# SwitchDecoder.net
KiCad netlist of a schematic drawn in Altium Designer
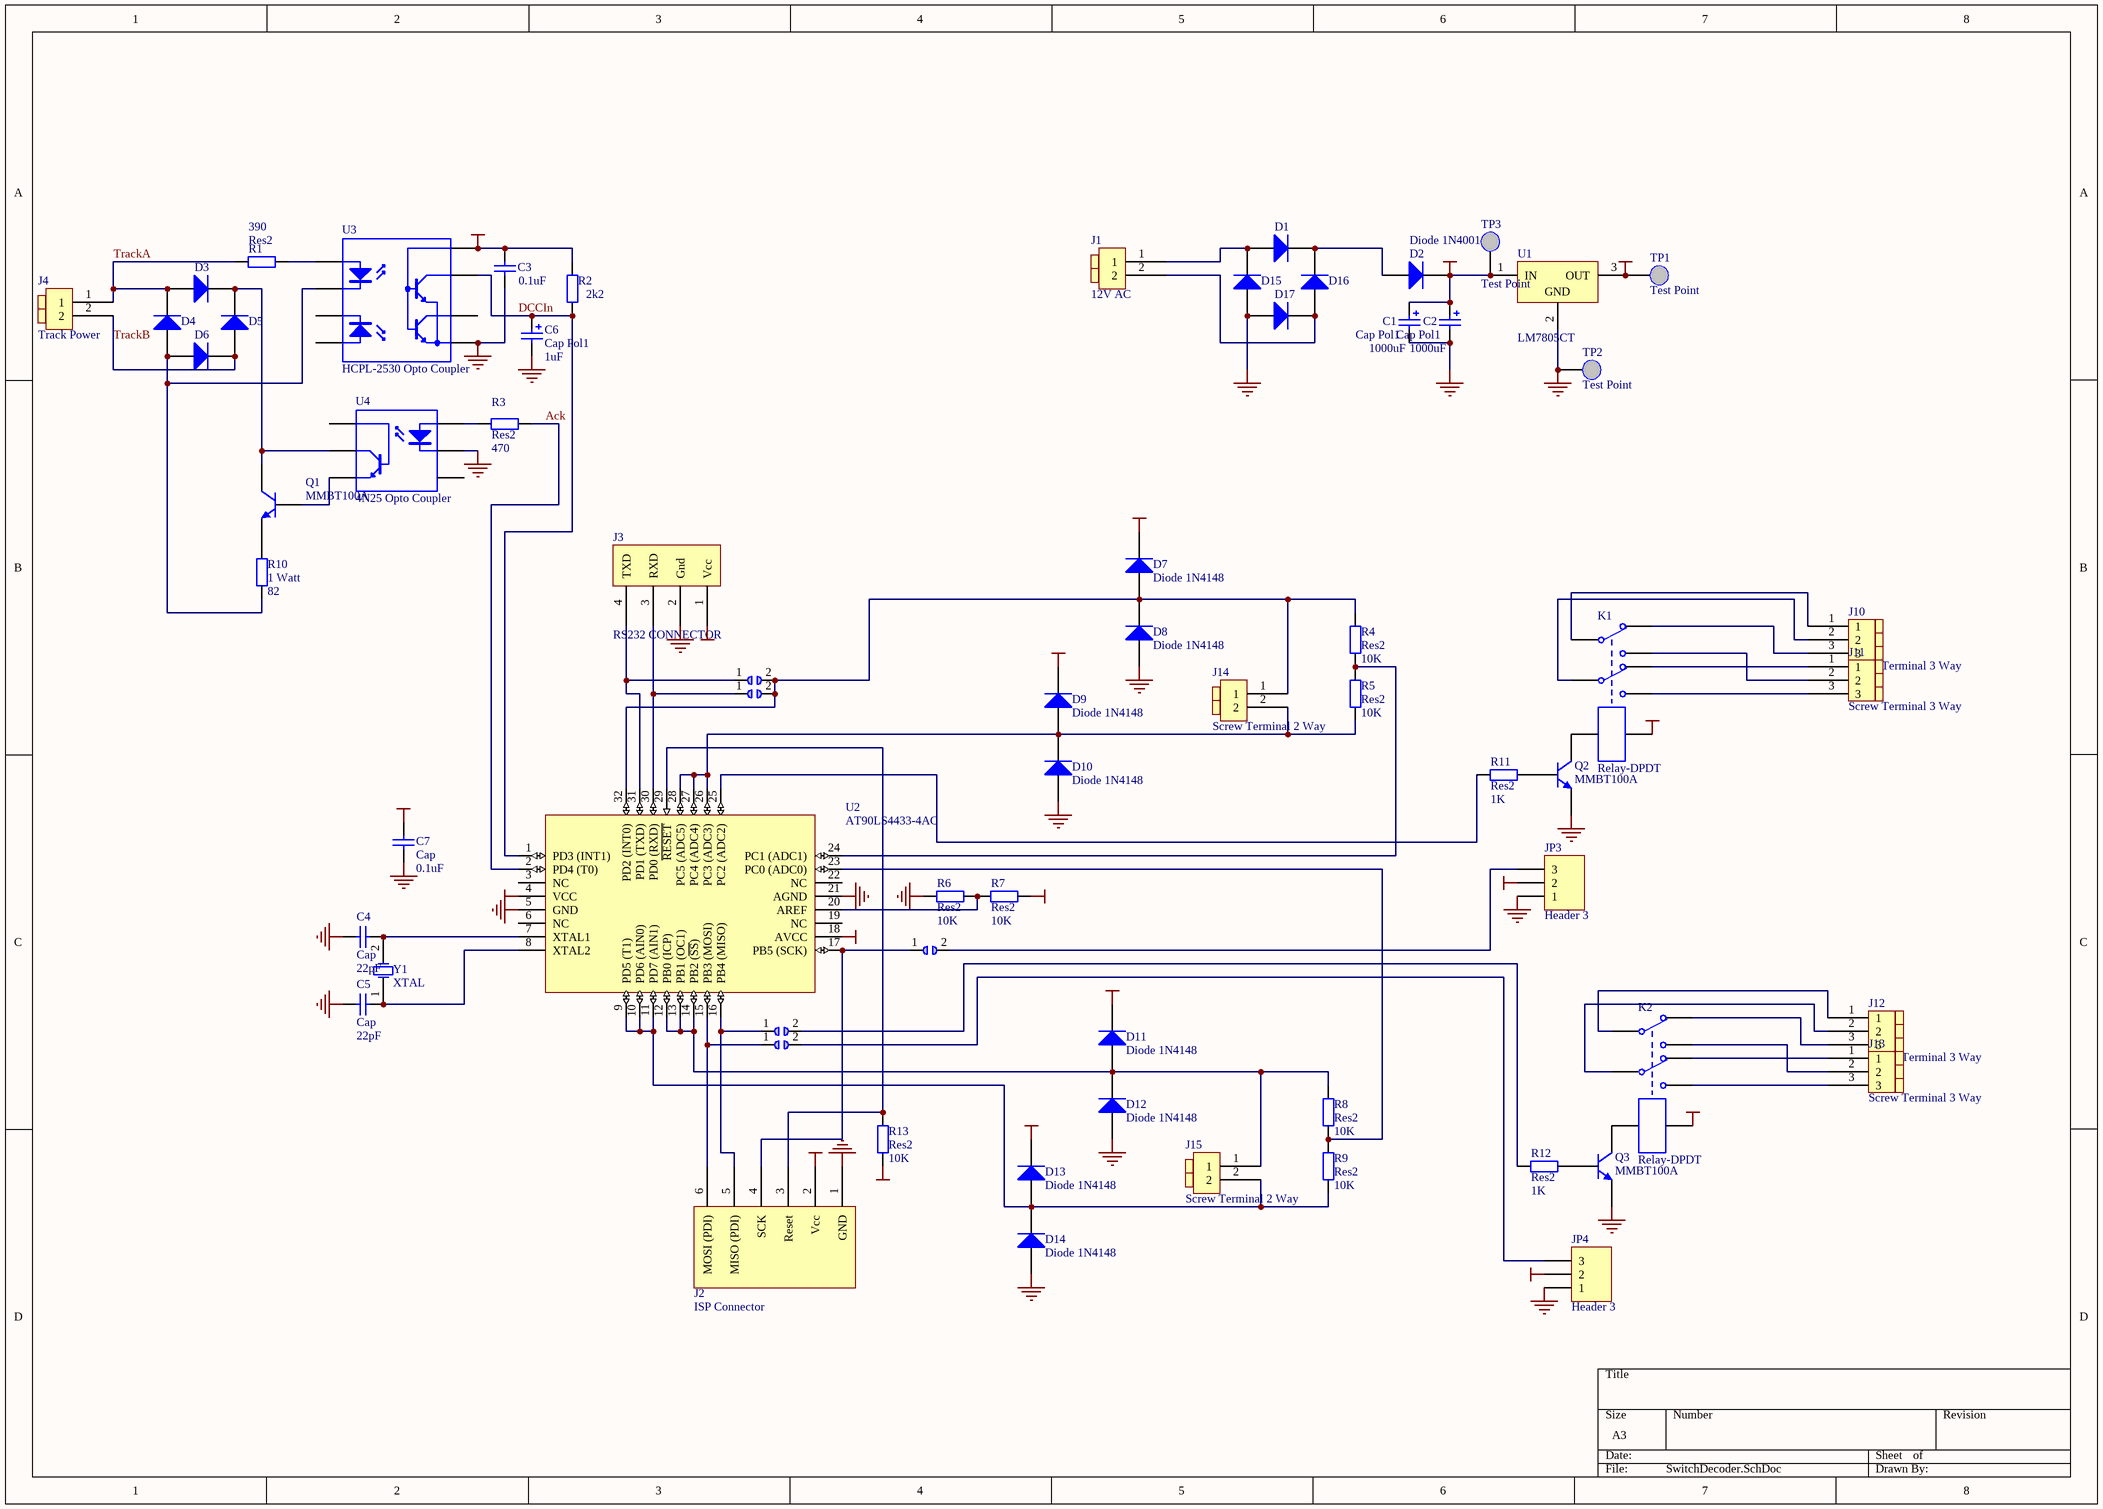
[diagram p0: SwitchDecoder.SchDoc]

(export (version "E")
  (design (tool "Eeschema 10.0.6"))
  (components
    (comp (ref "C1")
      (value "Cap Pol1")
      (footprint "CAPPR5-10X10.5")
      (description "Polarized Capacitor (Radial)")
      (fields (field (name "ALTIUM_VALUE") "1000uF") (field (name "PUBLISHER") "Altium Limited"))
      (libsource (lib "Miscellaneous Devices") (part "Cap Pol1"))
    )
    (comp (ref "C2")
      (value "Cap Pol1")
      (footprint "CAPPR5-10X10.5")
      (description "Polarized Capacitor (Radial)")
      (fields (field (name "ALTIUM_VALUE") "1000uF") (field (name "PUBLISHER") "Altium Limited"))
      (libsource (lib "Miscellaneous Devices") (part "Cap Pol1"))
    )
    (comp (ref "C3")
      (value "0.1uF")
      (footprint "CC2012-0805")
      (description "Capacitor")
      (fields (field (name "Comment") "Cap") (field (name "PUBLISHER") "Altium Limited"))
      (libsource (lib "Miscellaneous Devices") (part "Cap"))
    )
    (comp (ref "C4")
      (value "Cap")
      (footprint "CC2012-0805")
      (description "Capacitor")
      (fields (field (name "ALTIUM_VALUE") "22pF") (field (name "PUBLISHER") "Altium Limited"))
      (libsource (lib "Miscellaneous Devices") (part "Cap"))
    )
    (comp (ref "C5")
      (value "Cap")
      (footprint "CC2012-0805")
      (description "Capacitor")
      (fields (field (name "ALTIUM_VALUE") "22pF") (field (name "PUBLISHER") "Altium Limited"))
      (libsource (lib "Miscellaneous Devices") (part "Cap"))
    )
    (comp (ref "C6")
      (value "Cap Pol1")
      (footprint "CC3216-1206")
      (description "Polarized Capacitor (Radial)")
      (fields (field (name "ALTIUM_VALUE") "1uF") (field (name "PUBLISHER") "Altium Limited"))
      (libsource (lib "Miscellaneous Devices") (part "Cap Pol1"))
    )
    (comp (ref "C7")
      (value "Cap")
      (footprint "CC2012-0805")
      (description "Capacitor")
      (fields (field (name "ALTIUM_VALUE") "0.1uF") (field (name "PUBLISHER") "Altium Limited"))
      (libsource (lib "Miscellaneous Devices") (part "Cap"))
    )
    (comp (ref "D1")
      (value "Diode 1N4004")
      (footprint "DIO10.46-5.3x2.8")
      (description "1 Amp General Purpose Rectifier")
      (fields (field (name "PUBLISHER") "Altium Limited"))
      (libsource (lib "Miscellaneous Devices") (part "Diode 1N4004"))
    )
    (comp (ref "D2")
      (value "Diode 1N4001")
      (footprint "DIO10.46-5.3x2.8")
      (description "1 Amp General Purpose Rectifier")
      (fields (field (name "PUBLISHER") "Altium Limited"))
      (libsource (lib "Miscellaneous Devices") (part "Diode 1N4001"))
    )
    (comp (ref "D3")
      (value "Diode 1N4148")
      (footprint "DIO7.1-3.9x1.9")
      (description "High Conductance Fast Diode")
      (fields (field (name "PUBLISHER") "Altium Limited"))
      (libsource (lib "Miscellaneous Devices") (part "Diode 1N4148"))
    )
    (comp (ref "D4")
      (value "Diode 1N4148")
      (footprint "DIO7.1-3.9x1.9")
      (description "High Conductance Fast Diode")
      (fields (field (name "PUBLISHER") "Altium Limited"))
      (libsource (lib "Miscellaneous Devices") (part "Diode 1N4148"))
    )
    (comp (ref "D5")
      (value "Diode 1N4148")
      (footprint "DIO7.1-3.9x1.9")
      (description "High Conductance Fast Diode")
      (fields (field (name "PUBLISHER") "Altium Limited"))
      (libsource (lib "Miscellaneous Devices") (part "Diode 1N4148"))
    )
    (comp (ref "D6")
      (value "Diode 1N4148")
      (footprint "DIO7.1-3.9x1.9")
      (description "High Conductance Fast Diode")
      (fields (field (name "PUBLISHER") "Altium Limited"))
      (libsource (lib "Miscellaneous Devices") (part "Diode 1N4148"))
    )
    (comp (ref "D7")
      (value "Diode 1N4148")
      (footprint "DIO7.1-3.9x1.9")
      (description "High Conductance Fast Diode")
      (fields (field (name "PUBLISHER") "Altium Limited"))
      (libsource (lib "Miscellaneous Devices") (part "Diode 1N4148"))
    )
    (comp (ref "D8")
      (value "Diode 1N4148")
      (footprint "DIO7.1-3.9x1.9")
      (description "High Conductance Fast Diode")
      (fields (field (name "PUBLISHER") "Altium Limited"))
      (libsource (lib "Miscellaneous Devices") (part "Diode 1N4148"))
    )
    (comp (ref "D9")
      (value "Diode 1N4148")
      (footprint "DIO7.1-3.9x1.9")
      (description "High Conductance Fast Diode")
      (fields (field (name "PUBLISHER") "Altium Limited"))
      (libsource (lib "Miscellaneous Devices") (part "Diode 1N4148"))
    )
    (comp (ref "D10")
      (value "Diode 1N4148")
      (footprint "DIO7.1-3.9x1.9")
      (description "High Conductance Fast Diode")
      (fields (field (name "PUBLISHER") "Altium Limited"))
      (libsource (lib "Miscellaneous Devices") (part "Diode 1N4148"))
    )
    (comp (ref "D11")
      (value "Diode 1N4148")
      (footprint "DIO7.1-3.9x1.9")
      (description "High Conductance Fast Diode")
      (fields (field (name "PUBLISHER") "Altium Limited"))
      (libsource (lib "Miscellaneous Devices") (part "Diode 1N4148"))
    )
    (comp (ref "D12")
      (value "Diode 1N4148")
      (footprint "DIO7.1-3.9x1.9")
      (description "High Conductance Fast Diode")
      (fields (field (name "PUBLISHER") "Altium Limited"))
      (libsource (lib "Miscellaneous Devices") (part "Diode 1N4148"))
    )
    (comp (ref "D13")
      (value "Diode 1N4148")
      (footprint "DIO7.1-3.9x1.9")
      (description "High Conductance Fast Diode")
      (fields (field (name "PUBLISHER") "Altium Limited"))
      (libsource (lib "Miscellaneous Devices") (part "Diode 1N4148"))
    )
    (comp (ref "D14")
      (value "Diode 1N4148")
      (footprint "DIO7.1-3.9x1.9")
      (description "High Conductance Fast Diode")
      (fields (field (name "PUBLISHER") "Altium Limited"))
      (libsource (lib "Miscellaneous Devices") (part "Diode 1N4148"))
    )
    (comp (ref "D15")
      (value "Diode 1N4004")
      (footprint "DIO10.46-5.3x2.8")
      (description "1 Amp General Purpose Rectifier")
      (fields (field (name "PUBLISHER") "Altium Limited"))
      (libsource (lib "Miscellaneous Devices") (part "Diode 1N4004"))
    )
    (comp (ref "D16")
      (value "Diode 1N4004")
      (footprint "DIO10.46-5.3x2.8")
      (description "1 Amp General Purpose Rectifier")
      (fields (field (name "PUBLISHER") "Altium Limited"))
      (libsource (lib "Miscellaneous Devices") (part "Diode 1N4004"))
    )
    (comp (ref "D17")
      (value "Diode 1N4004")
      (footprint "DIO10.46-5.3x2.8")
      (description "1 Amp General Purpose Rectifier")
      (fields (field (name "PUBLISHER") "Altium Limited"))
      (libsource (lib "Miscellaneous Devices") (part "Diode 1N4004"))
    )
    (comp (ref "J1")
      (value "12V AC")
      (footprint "Screw Terminal 2 way 0.2")
      (libsource (lib "Custom") (part "Screw Terminal 2 Way"))
    )
    (comp (ref "J2")
      (value "ISP Connector")
      (footprint "0.1 SIP 6 PIN")
      (libsource (lib "Custom") (part "ISP Connector"))
    )
    (comp (ref "J3")
      (value "RS232 CONNECTOR")
      (footprint "0.1 SIP 4 PIN")
      (libsource (lib "Custom") (part "RS232 CONNECTOR"))
    )
    (comp (ref "J4")
      (value "Track Power")
      (footprint "Screw Terminal 2 way 0.2")
      (libsource (lib "Custom") (part "Screw Terminal 2 Way"))
    )
    (comp (ref "J5") (value "Jumper") (footprint "Jumper") (libsource (lib "Custom") (part "Jumper")))
    (comp (ref "J6") (value "Jumper") (footprint "Jumper") (libsource (lib "Custom") (part "Jumper")))
    (comp (ref "J7") (value "Jumper") (footprint "Jumper") (libsource (lib "Custom") (part "Jumper")))
    (comp (ref "J8") (value "Jumper") (footprint "Jumper") (libsource (lib "Custom") (part "Jumper")))
    (comp (ref "J9") (value "Jumper") (footprint "Jumper") (libsource (lib "Custom") (part "Jumper")))
    (comp (ref "J10")
      (value "Screw Terminal 3 Way")
      (footprint "Screw Terminal 3 way 0.2")
      (libsource (lib "Custom") (part "Screw Terminal 3 Way"))
    )
    (comp (ref "J11")
      (value "Screw Terminal 3 Way")
      (footprint "Screw Terminal 3 way 0.2")
      (libsource (lib "Custom") (part "Screw Terminal 3 Way"))
    )
    (comp (ref "J12")
      (value "Screw Terminal 3 Way")
      (footprint "Screw Terminal 3 way 0.2")
      (libsource (lib "Custom") (part "Screw Terminal 3 Way"))
    )
    (comp (ref "J13")
      (value "Screw Terminal 3 Way")
      (footprint "Screw Terminal 3 way 0.2")
      (libsource (lib "Custom") (part "Screw Terminal 3 Way"))
    )
    (comp (ref "J14")
      (value "Screw Terminal 2 Way")
      (footprint "Screw Terminal 2 way 0.2")
      (libsource (lib "Custom") (part "Screw Terminal 2 Way"))
    )
    (comp (ref "J15")
      (value "Screw Terminal 2 Way")
      (footprint "Screw Terminal 2 way 0.2")
      (libsource (lib "Custom") (part "Screw Terminal 2 Way"))
    )
    (comp (ref "JP3")
      (value "Header 3")
      (footprint "HDR1X3")
      (description "Header, 3-Pin")
      (fields (field (name "PUBLISHER") "Altium Limited"))
      (libsource (lib "Miscellaneous Connectors") (part "Header 3"))
    )
    (comp (ref "JP4")
      (value "Header 3")
      (footprint "HDR1X3")
      (description "Header, 3-Pin")
      (fields (field (name "PUBLISHER") "Altium Limited"))
      (libsource (lib "Miscellaneous Connectors") (part "Header 3"))
    )
    (comp (ref "K1")
      (value "Relay-DPDT")
      (footprint "RelayDPDT")
      (description "Dual-Pole Dual-Throw Relay")
      (fields (field (name "PUBLISHER") "Altium Limited"))
      (libsource (lib "Miscellaneous Devices") (part "Relay-DPDT"))
    )
    (comp (ref "K2")
      (value "Relay-DPDT")
      (footprint "RelayDPDT")
      (description "Dual-Pole Dual-Throw Relay")
      (fields (field (name "PUBLISHER") "Altium Limited"))
      (libsource (lib "Miscellaneous Devices") (part "Relay-DPDT"))
    )
    (comp (ref "Q1")
      (value "MMBT100A")
      (footprint "SO-G3")
      (description "General Purpose Amplifier NPN Silicon")
      (fields (field (name "PUBLISHER") "Altium Limited"))
      (libsource (lib "Custom") (part "MMBT100A"))
    )
    (comp (ref "Q2")
      (value "MMBT100A")
      (footprint "SO-G3")
      (description "General Purpose Amplifier NPN Silicon")
      (fields (field (name "PUBLISHER") "Altium Limited"))
      (libsource (lib "Custom") (part "MMBT100A"))
    )
    (comp (ref "Q3")
      (value "MMBT100A")
      (footprint "SO-G3")
      (description "General Purpose Amplifier NPN Silicon")
      (fields (field (name "PUBLISHER") "Altium Limited"))
      (libsource (lib "Custom") (part "MMBT100A"))
    )
    (comp (ref "R1")
      (value "Res2")
      (footprint "CR2012-0805")
      (description "Resistor")
      (fields (field (name "ALTIUM_VALUE") "390") (field (name "PUBLISHER") "Altium Limited"))
      (libsource (lib "") (part "Res2_3"))
    )
    (comp (ref "R2")
      (value "2k2")
      (footprint "CR2012-0805")
      (description "Resistor")
      (fields (field (name "Comment") "Res2") (field (name "PUBLISHER") "Altium Limited"))
      (libsource (lib "Miscellaneous Devices") (part "Res2"))
    )
    (comp (ref "R3")
      (value "Res2")
      (footprint "CR2012-0805")
      (description "Resistor")
      (fields (field (name "ALTIUM_VALUE") "470") (field (name "PUBLISHER") "Altium Limited"))
      (libsource (lib "") (part "Res2_1"))
    )
    (comp (ref "R4")
      (value "Res2")
      (footprint "CR2012-0805")
      (description "Resistor")
      (fields (field (name "ALTIUM_VALUE") "10K") (field (name "PUBLISHER") "Altium Limited"))
      (libsource (lib "Miscellaneous Devices") (part "Res2"))
    )
    (comp (ref "R5")
      (value "Res2")
      (footprint "CR2012-0805")
      (description "Resistor")
      (fields (field (name "ALTIUM_VALUE") "10K") (field (name "PUBLISHER") "Altium Limited"))
      (libsource (lib "Miscellaneous Devices") (part "Res2"))
    )
    (comp (ref "R6")
      (value "Res2")
      (footprint "CR2012-0805")
      (description "Resistor")
      (fields (field (name "ALTIUM_VALUE") "10K") (field (name "PUBLISHER") "Altium Limited"))
      (libsource (lib "") (part "Res2_1"))
    )
    (comp (ref "R7")
      (value "Res2")
      (footprint "CR2012-0805")
      (description "Resistor")
      (fields (field (name "ALTIUM_VALUE") "10K") (field (name "PUBLISHER") "Altium Limited"))
      (libsource (lib "") (part "Res2_1"))
    )
    (comp (ref "R8")
      (value "Res2")
      (footprint "CR2012-0805")
      (description "Resistor")
      (fields (field (name "ALTIUM_VALUE") "10K") (field (name "PUBLISHER") "Altium Limited"))
      (libsource (lib "Miscellaneous Devices") (part "Res2"))
    )
    (comp (ref "R9")
      (value "Res2")
      (footprint "CR2012-0805")
      (description "Resistor")
      (fields (field (name "ALTIUM_VALUE") "10K") (field (name "PUBLISHER") "Altium Limited"))
      (libsource (lib "Miscellaneous Devices") (part "Res2"))
    )
    (comp (ref "R10")
      (value "1 Watt")
      (footprint "AXIAL-0.6")
      (description "Resistor")
      (fields (field (name "ALTIUM_VALUE") "82") (field (name "PUBLISHER") "Altium Limited"))
      (libsource (lib "") (part "Res2_2"))
    )
    (comp (ref "R11")
      (value "Res2")
      (footprint "CR2012-0805")
      (description "Resistor")
      (fields (field (name "ALTIUM_VALUE") "1K") (field (name "PUBLISHER") "Altium Limited"))
      (libsource (lib "") (part "Res2_1"))
    )
    (comp (ref "R12")
      (value "Res2")
      (footprint "CR2012-0805")
      (description "Resistor")
      (fields (field (name "ALTIUM_VALUE") "1K") (field (name "PUBLISHER") "Altium Limited"))
      (libsource (lib "") (part "Res2_1"))
    )
    (comp (ref "R13")
      (value "Res2")
      (footprint "CR2012-0805")
      (description "Resistor")
      (fields (field (name "ALTIUM_VALUE") "10K") (field (name "PUBLISHER") "Altium Limited"))
      (libsource (lib "Miscellaneous Devices") (part "Res2"))
    )
    (comp (ref "TP1")
      (value "Test Point")
      (footprint "TestPoint")
      (libsource (lib "Custom") (part "TestPoint"))
    )
    (comp (ref "TP2")
      (value "Test Point")
      (footprint "TestPoint")
      (libsource (lib "Custom") (part "TestPoint"))
    )
    (comp (ref "TP3")
      (value "Test Point")
      (footprint "TestPoint")
      (libsource (lib "Custom") (part "TestPoint"))
    )
    (comp (ref "U1")
      (value "LM7805CT")
      (footprint "TO-3 with HS Clip")
      (description "Series 3-Terminal Positive Regulator")
      (fields (field (name "PUBLISHER") "Altium Limited"))
      (libsource (lib "NSC Power Mgt Voltage Regulator") (part "LM7805CT"))
    )
    (comp (ref "U2")
      (value "AT90LS4433-4AC")
      (footprint "32A")
      (description "8-Bit AVR Microcontroller with 4K Bytes of In-System Programmable Flash Memory")
      (fields (field (name "PUBLISHER") "Altium Limited"))
      (libsource (lib "Custom") (part "AT90LS4433-4AC"))
    )
    (comp (ref "U3")
      (value "HCPL-2530 Opto Coupler")
      (footprint "8P3")
      (libsource (lib "Custom") (part "HCPL-2530"))
    )
    (comp (ref "U4") (value "4N25 Opto Coupler") (footprint "DIP6") (libsource (lib "Custom") (part "4N25")))
    (comp (ref "Y1")
      (value "XTAL")
      (footprint "RAD-0.2")
      (description "Crystal Oscillator")
      (fields (field (name "PUBLISHER") "Altium Limited"))
      (libsource (lib "Miscellaneous Devices") (part "XTAL"))
    )
  )
  (nets
    (net (code "1") (name "/Ack") (class "Default")
      (node (ref "R3") (pin "2") (pinfunction "2_2") (pintype "passive"))
      (node (ref "U2") (pin "2") (pinfunction "PD4_(T0)_2") (pintype "bidirectional"))
    )
    (net (code "2") (name "/DCCIn") (class "Default")
      (node (ref "C6") (pin "1") (pinfunction "1_1") (pintype "passive"))
      (node (ref "R2") (pin "1") (pinfunction "1_1") (pintype "passive"))
      (node (ref "U2") (pin "1") (pinfunction "PD3_(INT1)_1") (pintype "bidirectional"))
      (node (ref "U3") (pin "7") (pinfunction "C_7") (pintype "passive"))
    )
    (net (code "3") (name "/TrackA") (class "Default")
      (node (ref "D3") (pin "1") (pinfunction "A_1") (pintype "passive"))
      (node (ref "D4") (pin "2") (pinfunction "K_2") (pintype "passive"))
      (node (ref "J4") (pin "1") (pinfunction "1_1") (pintype "passive"))
      (node (ref "R1") (pin "2") (pinfunction "2_2") (pintype "passive"))
    )
    (net (code "4") (name "/TrackB") (class "Default")
      (node (ref "D5") (pin "1") (pinfunction "A_1") (pintype "passive"))
      (node (ref "D6") (pin "2") (pinfunction "K_2") (pintype "passive"))
      (node (ref "J4") (pin "2") (pinfunction "2_2") (pintype "passive"))
    )
    (net (code "5") (name "GND") (class "Default")
      (node (ref "C1") (pin "2") (pinfunction "2_2") (pintype "passive"))
      (node (ref "C2") (pin "2") (pinfunction "2_2") (pintype "passive"))
      (node (ref "C3") (pin "1") (pinfunction "1_1") (pintype "passive"))
      (node (ref "C4") (pin "1") (pinfunction "1_1") (pintype "passive"))
      (node (ref "C5") (pin "1") (pinfunction "1_1") (pintype "passive"))
      (node (ref "C6") (pin "2") (pinfunction "2_2") (pintype "passive"))
      (node (ref "C7") (pin "1") (pinfunction "1_1") (pintype "passive"))
      (node (ref "D10") (pin "1") (pinfunction "A_1") (pintype "passive"))
      (node (ref "D12") (pin "1") (pinfunction "A_1") (pintype "passive"))
      (node (ref "D14") (pin "1") (pinfunction "A_1") (pintype "passive"))
      (node (ref "D15") (pin "1") (pinfunction "A_1") (pintype "passive"))
      (node (ref "D17") (pin "1") (pinfunction "A_1") (pintype "passive"))
      (node (ref "D8") (pin "1") (pinfunction "A_1") (pintype "passive"))
      (node (ref "J2") (pin "1") (pinfunction "GND_1") (pintype "passive"))
      (node (ref "J3") (pin "2") (pinfunction "Gnd_2") (pintype "passive"))
      (node (ref "JP3") (pin "1") (pinfunction "1_1") (pintype "passive"))
      (node (ref "JP4") (pin "1") (pinfunction "1_1") (pintype "passive"))
      (node (ref "Q2") (pin "2") (pinfunction "E_2") (pintype "passive"))
      (node (ref "Q3") (pin "2") (pinfunction "E_2") (pintype "passive"))
      (node (ref "R6") (pin "1") (pinfunction "1_1") (pintype "passive"))
      (node (ref "TP2") (pin "1") (pintype "passive"))
      (node (ref "U1") (pin "2") (pinfunction "GND_2") (pintype "power_in"))
      (node (ref "U2") (pin "21") (pinfunction "AGND_21") (pintype "power_in"))
      (node (ref "U2") (pin "5") (pinfunction "GND_5") (pintype "power_in"))
      (node (ref "U3") (pin "5") (pinfunction "E_5") (pintype "passive"))
      (node (ref "U4") (pin "2") (pinfunction "K_2") (pintype "passive"))
    )
    (net (code "6") (name "Net-(D1-A)") (class "Default")
      (node (ref "D1") (pin "1") (pinfunction "A_1") (pintype "passive"))
      (node (ref "D15") (pin "2") (pinfunction "K_2") (pintype "passive"))
      (node (ref "J1") (pin "1") (pinfunction "1_1") (pintype "passive"))
    )
    (net (code "7") (name "Net-(D1-K)") (class "Default")
      (node (ref "D1") (pin "2") (pinfunction "K_2") (pintype "passive"))
      (node (ref "D16") (pin "2") (pinfunction "K_2") (pintype "passive"))
      (node (ref "D2") (pin "1") (pinfunction "A_1") (pintype "passive"))
    )
    (net (code "8") (name "Net-(D3-K)") (class "Default")
      (node (ref "D3") (pin "2") (pinfunction "K_2") (pintype "passive"))
      (node (ref "D5") (pin "2") (pinfunction "K_2") (pintype "passive"))
      (node (ref "Q1") (pin "3") (pinfunction "C_3") (pintype "passive"))
      (node (ref "U4") (pin "5") (pinfunction "C_5") (pintype "passive"))
    )
    (net (code "9") (name "Net-(D4-A)") (class "Default")
      (node (ref "D4") (pin "1") (pinfunction "A_1") (pintype "passive"))
      (node (ref "D6") (pin "1") (pinfunction "A_1") (pintype "passive"))
      (node (ref "R10") (pin "2") (pinfunction "2_2") (pintype "passive"))
      (node (ref "U3") (pin "2") (pinfunction "K_2") (pintype "passive"))
    )
    (net (code "10") (name "Net-(D7-A)") (class "Default")
      (node (ref "D7") (pin "1") (pinfunction "A_1") (pintype "passive"))
      (node (ref "D8") (pin "2") (pinfunction "K_2") (pintype "passive"))
      (node (ref "J14") (pin "1") (pinfunction "1_1") (pintype "passive"))
      (node (ref "J5") (pin "2") (pintype "passive"))
      (node (ref "J6") (pin "2") (pintype "passive"))
      (node (ref "R4") (pin "2") (pinfunction "2_2") (pintype "passive"))
      (node (ref "U2") (pin "32") (pinfunction "PD2_(INT0)_32") (pintype "bidirectional"))
    )
    (net (code "11") (name "Net-(D10-K)") (class "Default")
      (node (ref "D10") (pin "2") (pinfunction "K_2") (pintype "passive"))
      (node (ref "D9") (pin "1") (pinfunction "A_1") (pintype "passive"))
      (node (ref "J14") (pin "2") (pinfunction "2_2") (pintype "passive"))
      (node (ref "R5") (pin "1") (pinfunction "1_1") (pintype "passive"))
      (node (ref "U2") (pin "26") (pinfunction "PC3_(ADC3)_26") (pintype "bidirectional"))
      (node (ref "U2") (pin "27") (pinfunction "PC4_(ADC4)_27") (pintype "bidirectional"))
      (node (ref "U2") (pin "28") (pinfunction "PC5_(ADC5)_28") (pintype "bidirectional"))
    )
    (net (code "12") (name "Net-(D11-A)") (class "Default")
      (node (ref "D11") (pin "1") (pinfunction "A_1") (pintype "passive"))
      (node (ref "D12") (pin "2") (pinfunction "K_2") (pintype "passive"))
      (node (ref "J15") (pin "1") (pinfunction "1_1") (pintype "passive"))
      (node (ref "R8") (pin "2") (pinfunction "2_2") (pintype "passive"))
      (node (ref "U2") (pin "12") (pinfunction "PB0_(ICP)_12") (pintype "bidirectional"))
      (node (ref "U2") (pin "13") (pinfunction "PB1_(OC1)_13") (pintype "bidirectional"))
      (node (ref "U2") (pin "14") (pinfunction "PB2_(~{SS})_14") (pintype "bidirectional"))
    )
    (net (code "13") (name "Net-(D13-A)") (class "Default")
      (node (ref "D13") (pin "1") (pinfunction "A_1") (pintype "passive"))
      (node (ref "D14") (pin "2") (pinfunction "K_2") (pintype "passive"))
      (node (ref "J15") (pin "2") (pinfunction "2_2") (pintype "passive"))
      (node (ref "R9") (pin "1") (pinfunction "1_1") (pintype "passive"))
      (node (ref "U2") (pin "10") (pinfunction "PD6_(AIN0)_10") (pintype "bidirectional"))
      (node (ref "U2") (pin "11") (pinfunction "PD7_(AIN1)_11") (pintype "bidirectional"))
      (node (ref "U2") (pin "9") (pinfunction "PD5_(T1)_9") (pintype "bidirectional"))
    )
    (net (code "14") (name "Net-(D16-A)") (class "Default")
      (node (ref "D16") (pin "1") (pinfunction "A_1") (pintype "passive"))
      (node (ref "D17") (pin "2") (pinfunction "K_2") (pintype "passive"))
      (node (ref "J1") (pin "2") (pinfunction "2_2") (pintype "passive"))
    )
    (net (code "15") (name "Net-(J2-MISO_(PDI))") (class "Default")
      (node (ref "J2") (pin "5") (pinfunction "MISO_(PDI)_5") (pintype "passive"))
      (node (ref "J8") (pin "1") (pintype "passive"))
      (node (ref "U2") (pin "16") (pinfunction "PB4_(MISO)_16") (pintype "bidirectional"))
    )
    (net (code "16") (name "Net-(J2-MOSI_(PDI))") (class "Default")
      (node (ref "J2") (pin "6") (pinfunction "MOSI_(PDI)_6") (pintype "passive"))
      (node (ref "J9") (pin "1") (pintype "passive"))
      (node (ref "U2") (pin "15") (pinfunction "PB3_(MOSI)_15") (pintype "bidirectional"))
    )
    (net (code "17") (name "Net-(J2-Reset)") (class "Default")
      (node (ref "J2") (pin "3") (pinfunction "Reset_3") (pintype "passive"))
      (node (ref "R13") (pin "2") (pinfunction "2_2") (pintype "passive"))
      (node (ref "U2") (pin "29") (pinfunction "~{RESET}_29") (pintype "input"))
    )
    (net (code "18") (name "Net-(J2-SCK)") (class "Default")
      (node (ref "J2") (pin "4") (pinfunction "SCK_4") (pintype "passive"))
      (node (ref "J7") (pin "1") (pintype "passive"))
      (node (ref "U2") (pin "17") (pinfunction "PB5_(SCK)_17") (pintype "bidirectional"))
    )
    (net (code "19") (name "Net-(J3-RXD)") (class "Default")
      (node (ref "J3") (pin "3") (pinfunction "RXD_3") (pintype "passive"))
      (node (ref "J6") (pin "1") (pintype "passive"))
      (node (ref "U2") (pin "30") (pinfunction "PD0_(RXD)_30") (pintype "bidirectional"))
    )
    (net (code "20") (name "Net-(J3-TXD)") (class "Default")
      (node (ref "J3") (pin "4") (pinfunction "TXD_4") (pintype "passive"))
      (node (ref "J5") (pin "1") (pintype "passive"))
      (node (ref "U2") (pin "31") (pinfunction "PD1_(TXD)_31") (pintype "bidirectional"))
    )
    (net (code "21") (name "Net-(J7-Pad2)") (class "Default")
      (node (ref "J7") (pin "2") (pintype "passive"))
      (node (ref "JP3") (pin "3") (pinfunction "3_3") (pintype "passive"))
    )
    (net (code "22") (name "Net-(J8-Pad2)") (class "Default")
      (node (ref "J8") (pin "2") (pintype "passive"))
      (node (ref "R12") (pin "1") (pinfunction "1_1") (pintype "passive"))
    )
    (net (code "23") (name "Net-(J9-Pad2)") (class "Default")
      (node (ref "J9") (pin "2") (pintype "passive"))
      (node (ref "JP4") (pin "3") (pinfunction "3_3") (pintype "passive"))
    )
    (net (code "24") (name "Net-(J10-Pad1)") (class "Default")
      (node (ref "J10") (pin "1") (pinfunction "1_1") (pintype "passive"))
      (node (ref "K1") (pin "1") (pinfunction "1_1") (pintype "passive"))
    )
    (net (code "25") (name "Net-(J10-Pad2)") (class "Default")
      (node (ref "J10") (pin "2") (pinfunction "2_2") (pintype "passive"))
      (node (ref "K1") (pin "4") (pinfunction "4_4") (pintype "passive"))
    )
    (net (code "26") (name "Net-(J10-Pad3)") (class "Default")
      (node (ref "J10") (pin "3") (pinfunction "3_3") (pintype "passive"))
      (node (ref "K1") (pin "2") (pinfunction "2_2") (pintype "passive"))
    )
    (net (code "27") (name "Net-(J11-Pad1)") (class "Default")
      (node (ref "J11") (pin "1") (pinfunction "1_1") (pintype "passive"))
      (node (ref "K1") (pin "5") (pinfunction "5_5") (pintype "passive"))
    )
    (net (code "28") (name "Net-(J11-Pad2)") (class "Default")
      (node (ref "J11") (pin "2") (pinfunction "2_2") (pintype "passive"))
      (node (ref "K1") (pin "3") (pinfunction "3_3") (pintype "passive"))
    )
    (net (code "29") (name "Net-(J11-Pad3)") (class "Default")
      (node (ref "J11") (pin "3") (pinfunction "3_3") (pintype "passive"))
      (node (ref "K1") (pin "6") (pinfunction "6_6") (pintype "passive"))
    )
    (net (code "30") (name "Net-(J12-Pad1)") (class "Default")
      (node (ref "J12") (pin "1") (pinfunction "1_1") (pintype "passive"))
      (node (ref "K2") (pin "1") (pinfunction "1_1") (pintype "passive"))
    )
    (net (code "31") (name "Net-(J12-Pad2)") (class "Default")
      (node (ref "J12") (pin "2") (pinfunction "2_2") (pintype "passive"))
      (node (ref "K2") (pin "4") (pinfunction "4_4") (pintype "passive"))
    )
    (net (code "32") (name "Net-(J12-Pad3)") (class "Default")
      (node (ref "J12") (pin "3") (pinfunction "3_3") (pintype "passive"))
      (node (ref "K2") (pin "2") (pinfunction "2_2") (pintype "passive"))
    )
    (net (code "33") (name "Net-(J13-Pad1)") (class "Default")
      (node (ref "J13") (pin "1") (pinfunction "1_1") (pintype "passive"))
      (node (ref "K2") (pin "5") (pinfunction "5_5") (pintype "passive"))
    )
    (net (code "34") (name "Net-(J13-Pad2)") (class "Default")
      (node (ref "J13") (pin "2") (pinfunction "2_2") (pintype "passive"))
      (node (ref "K2") (pin "3") (pinfunction "3_3") (pintype "passive"))
    )
    (net (code "35") (name "Net-(J13-Pad3)") (class "Default")
      (node (ref "J13") (pin "3") (pinfunction "3_3") (pintype "passive"))
      (node (ref "K2") (pin "6") (pinfunction "6_6") (pintype "passive"))
    )
    (net (code "36") (name "Net-(Q1-B)") (class "Default")
      (node (ref "Q1") (pin "1") (pinfunction "B_1") (pintype "passive"))
      (node (ref "U4") (pin "4") (pinfunction "E_4") (pintype "passive"))
    )
    (net (code "37") (name "Net-(Q1-E)") (class "Default")
      (node (ref "Q1") (pin "2") (pinfunction "E_2") (pintype "passive"))
      (node (ref "R10") (pin "1") (pinfunction "1_1") (pintype "passive"))
    )
    (net (code "38") (name "Net-(Q2-B)") (class "Default")
      (node (ref "Q2") (pin "1") (pinfunction "B_1") (pintype "passive"))
      (node (ref "R11") (pin "2") (pinfunction "2_2") (pintype "passive"))
    )
    (net (code "39") (name "Net-(Q2-C)") (class "Default")
      (node (ref "K1") (pin "7") (pinfunction "7_7") (pintype "passive"))
      (node (ref "Q2") (pin "3") (pinfunction "C_3") (pintype "passive"))
    )
    (net (code "40") (name "Net-(Q3-B)") (class "Default")
      (node (ref "Q3") (pin "1") (pinfunction "B_1") (pintype "passive"))
      (node (ref "R12") (pin "2") (pinfunction "2_2") (pintype "passive"))
    )
    (net (code "41") (name "Net-(Q3-C)") (class "Default")
      (node (ref "K2") (pin "7") (pinfunction "7_7") (pintype "passive"))
      (node (ref "Q3") (pin "3") (pinfunction "C_3") (pintype "passive"))
    )
    (net (code "42") (name "Net-(R1-Pad1)") (class "Default")
      (node (ref "R1") (pin "1") (pinfunction "1_1") (pintype "passive"))
      (node (ref "U3") (pin "1") (pinfunction "A_1") (pintype "passive"))
    )
    (net (code "43") (name "Net-(R3-Pad1)") (class "Default")
      (node (ref "R3") (pin "1") (pinfunction "1_1") (pintype "passive"))
      (node (ref "U4") (pin "1") (pinfunction "K_1") (pintype "passive"))
    )
    (net (code "44") (name "Net-(U2-AREF)") (class "Default")
      (node (ref "R6") (pin "2") (pinfunction "2_2") (pintype "passive"))
      (node (ref "R7") (pin "1") (pinfunction "1_1") (pintype "passive"))
      (node (ref "U2") (pin "20") (pinfunction "AREF_20") (pintype "passive"))
    )
    (net (code "45") (name "Net-(U2-PC0_(ADC0))") (class "Default")
      (node (ref "R8") (pin "1") (pinfunction "1_1") (pintype "passive"))
      (node (ref "R9") (pin "2") (pinfunction "2_2") (pintype "passive"))
      (node (ref "U2") (pin "23") (pinfunction "PC0_(ADC0)_23") (pintype "bidirectional"))
    )
    (net (code "46") (name "Net-(U2-PC1_(ADC1))") (class "Default")
      (node (ref "R4") (pin "1") (pinfunction "1_1") (pintype "passive"))
      (node (ref "R5") (pin "2") (pinfunction "2_2") (pintype "passive"))
      (node (ref "U2") (pin "24") (pinfunction "PC1_(ADC1)_24") (pintype "bidirectional"))
    )
    (net (code "47") (name "Net-(U2-PC2_(ADC2))") (class "Default")
      (node (ref "R11") (pin "1") (pinfunction "1_1") (pintype "passive"))
      (node (ref "U2") (pin "25") (pinfunction "PC2_(ADC2)_25") (pintype "bidirectional"))
    )
    (net (code "48") (name "Net-(U2-XTAL1)") (class "Default")
      (node (ref "C4") (pin "2") (pinfunction "2_2") (pintype "passive"))
      (node (ref "U2") (pin "7") (pinfunction "XTAL1_7") (pintype "passive"))
      (node (ref "Y1") (pin "2") (pinfunction "OSC2_2") (pintype "passive"))
    )
    (net (code "49") (name "Net-(U2-XTAL2)") (class "Default")
      (node (ref "C5") (pin "2") (pinfunction "2_2") (pintype "passive"))
      (node (ref "U2") (pin "8") (pinfunction "XTAL2_8") (pintype "passive"))
      (node (ref "Y1") (pin "1") (pinfunction "OSC1_1") (pintype "passive"))
    )
    (net (code "50") (name "VCC") (class "Default")
      (node (ref "C3") (pin "2") (pinfunction "2_2") (pintype "passive"))
      (node (ref "C7") (pin "2") (pinfunction "2_2") (pintype "passive"))
      (node (ref "D11") (pin "2") (pinfunction "K_2") (pintype "passive"))
      (node (ref "D13") (pin "2") (pinfunction "K_2") (pintype "passive"))
      (node (ref "D7") (pin "2") (pinfunction "K_2") (pintype "passive"))
      (node (ref "D9") (pin "2") (pinfunction "K_2") (pintype "passive"))
      (node (ref "J2") (pin "2") (pinfunction "Vcc_2") (pintype "passive"))
      (node (ref "J3") (pin "1") (pinfunction "Vcc_1") (pintype "passive"))
      (node (ref "JP3") (pin "2") (pinfunction "2_2") (pintype "passive"))
      (node (ref "JP4") (pin "2") (pinfunction "2_2") (pintype "passive"))
      (node (ref "R13") (pin "1") (pinfunction "1_1") (pintype "passive"))
      (node (ref "R2") (pin "2") (pinfunction "2_2") (pintype "passive"))
      (node (ref "R7") (pin "2") (pinfunction "2_2") (pintype "passive"))
      (node (ref "TP1") (pin "1") (pintype "passive"))
      (node (ref "U1") (pin "3") (pinfunction "OUT_3") (pintype "power_in"))
      (node (ref "U2") (pin "18") (pinfunction "AVCC_18") (pintype "power_in"))
      (node (ref "U2") (pin "4") (pinfunction "VCC_4") (pintype "power_in"))
      (node (ref "U3") (pin "8") (pinfunction "E_8") (pintype "passive"))
    )
    (net (code "51") (name "Vdd") (class "Default")
      (node (ref "C1") (pin "1") (pinfunction "1_1") (pintype "passive"))
      (node (ref "C2") (pin "1") (pinfunction "1_1") (pintype "passive"))
      (node (ref "D2") (pin "2") (pinfunction "K_2") (pintype "passive"))
      (node (ref "K1") (pin "8") (pinfunction "8_8") (pintype "passive"))
      (node (ref "K2") (pin "8") (pinfunction "8_8") (pintype "passive"))
      (node (ref "TP3") (pin "1") (pintype "passive"))
      (node (ref "U1") (pin "1") (pinfunction "IN_1") (pintype "power_in"))
    )
    (net (code "52") (name "unconnected-(U2-NC-Pad3)") (class "Default")
      (node (ref "U2") (pin "3") (pinfunction "NC_3") (pintype "passive"))
    )
    (net (code "53") (name "unconnected-(U2-NC-Pad6)") (class "Default")
      (node (ref "U2") (pin "6") (pinfunction "NC_6") (pintype "passive"))
    )
    (net (code "54") (name "unconnected-(U2-NC-Pad19)") (class "Default")
      (node (ref "U2") (pin "19") (pinfunction "NC_19") (pintype "passive"))
    )
    (net (code "55") (name "unconnected-(U2-NC-Pad22)") (class "Default")
      (node (ref "U2") (pin "22") (pinfunction "NC_22") (pintype "passive"))
    )
    (net (code "56") (name "unconnected-(U3-A-Pad4)") (class "Default")
      (node (ref "U3") (pin "4") (pinfunction "A_4") (pintype "passive"))
    )
    (net (code "57") (name "unconnected-(U3-C-Pad6)") (class "Default")
      (node (ref "U3") (pin "6") (pinfunction "C_6") (pintype "passive"))
    )
    (net (code "58") (name "unconnected-(U3-K-Pad3)") (class "Default")
      (node (ref "U3") (pin "3") (pinfunction "K_3") (pintype "passive"))
    )
    (net (code "59") (name "unconnected-(U4-B-Pad6)") (class "Default")
      (node (ref "U4") (pin "6") (pinfunction "B_6") (pintype "passive"))
    )
    (net (code "60") (name "unconnected-(U4-N{slash}C-Pad3)") (class "Default")
      (node (ref "U4") (pin "3") (pinfunction "N/C_3") (pintype "passive"))
    )
  )
)
